# SSR_Switch.net
KiCad netlist of a schematic drawn in EasyEDA Pro
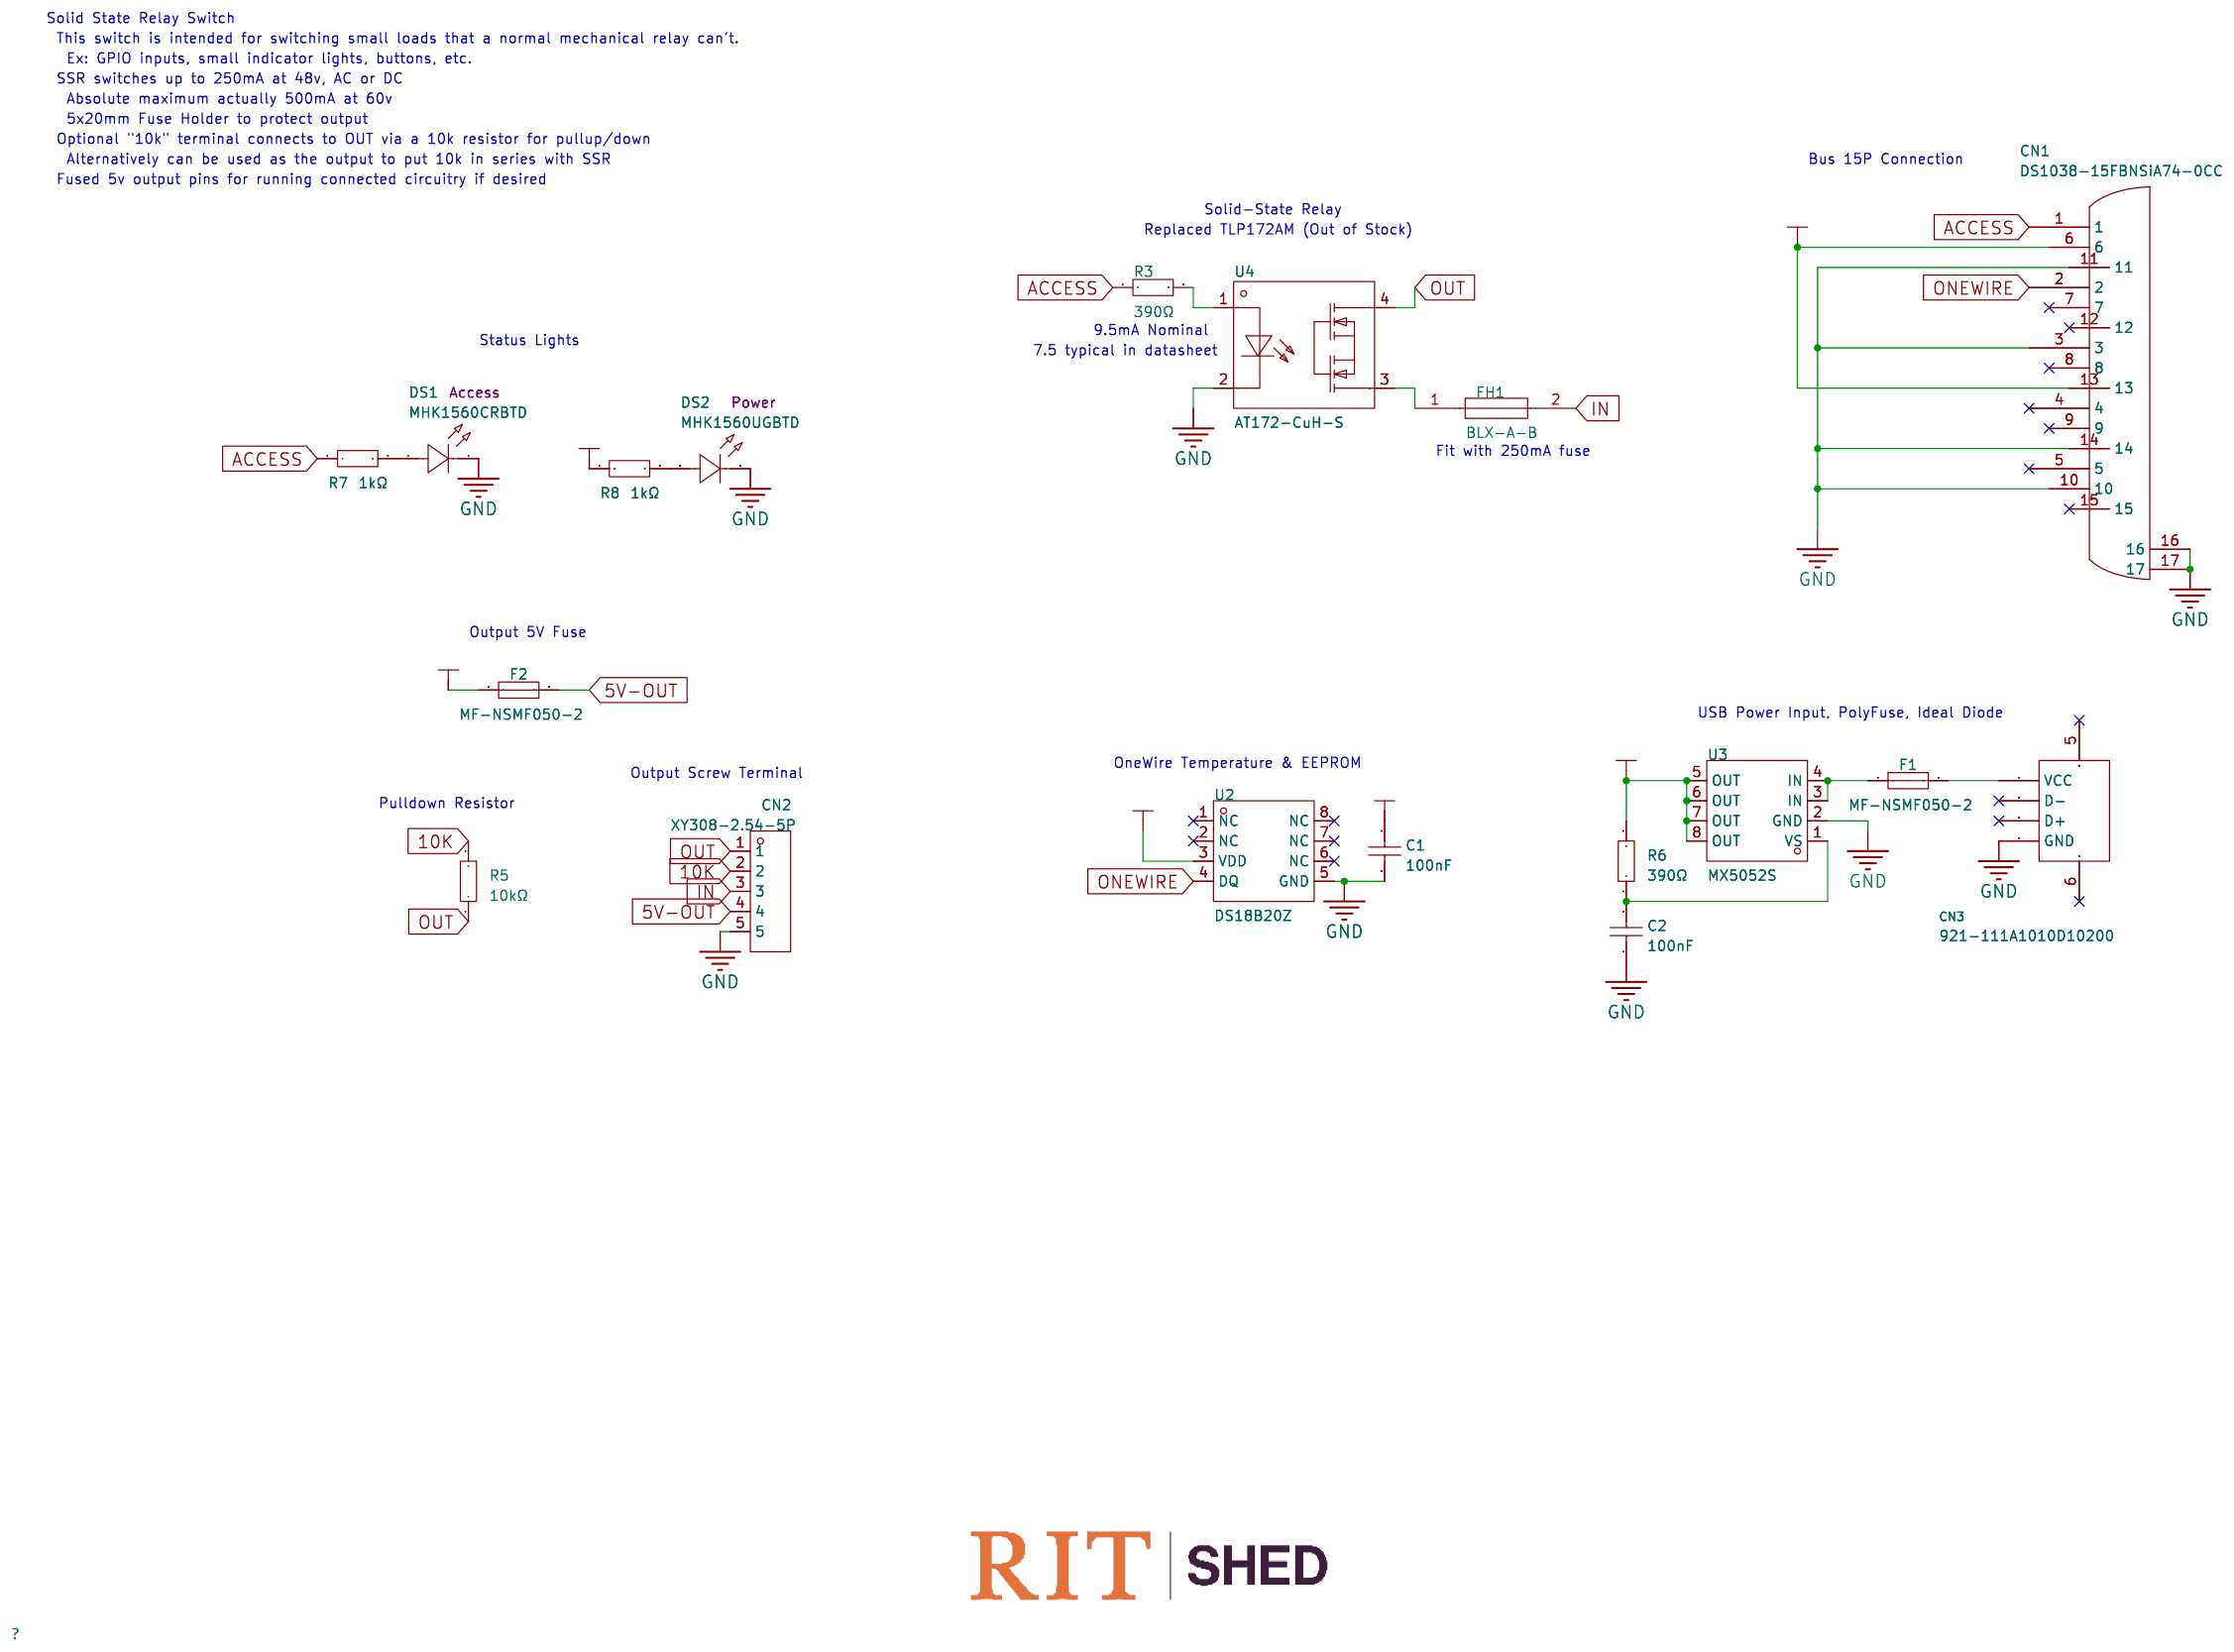
[diagram p0: schematic sheet]

(export (version "E")
  (design (tool "Eeschema 10.0.6"))
  (components
    (comp (ref "C1")
      (value "100nF")
      (footprint "easyedapro:C0805")
      (description "Capacitance:100nF Tolerance:±10% Tolerance:±10% Voltage Rating:100V Temperature Coefficient:X7R")
      (fields
        (field (name "Manufacturer Part") "CL21B104KCFNNNE")
        (field (name "Manufacturer") "SAMSUNG(三星)")
      )
      (libsource (lib "easyedapro") (part "CL21B104KCFNNNE"))
    )
    (comp (ref "C2")
      (value "100nF")
      (footprint "easyedapro:C0805")
      (description "Capacitance:100nF Tolerance:±10% Tolerance:±10% Voltage Rating:100V Temperature Coefficient:X7R")
      (fields
        (field (name "Manufacturer Part") "CL21B104KCFNNNE")
        (field (name "Manufacturer") "SAMSUNG(三星)")
      )
      (libsource (lib "easyedapro") (part "CL21B104KCFNNNE"))
    )
    (comp (ref "CN1")
      (value "DS1038-15FBNSiA74-0CC")
      (footprint "easyedapro:DSUB-TH_DS1038-15FBNSIA74-0CC")
      (fields (field (name "Manufacturer") "CONNFLY"))
      (libsource (lib "easyedapro") (part "DS1038-15FBNSIA74-0CC"))
    )
    (comp (ref "CN2")
      (value "XY308-2.54-5P")
      (footprint "easyedapro:CONN-TH_XY308-2.54-5P")
      (fields (field (name "Manufacturer") "XINLAIYA(新莱亚)"))
      (libsource (lib "easyedapro") (part "XY308-2.54-5P"))
    )
    (comp (ref "CN3")
      (value "921-111A1010D10200")
      (footprint "easyedapro:USB-B_TH_USB-B-FEMALE-90")
      (fields (field (name "Manufacturer") "精拓金"))
      (libsource (lib "easyedapro") (part "USB-B-Female-90"))
    )
    (comp (ref "DS1")
      (value "MHK1560CRBTD")
      (footprint "easyedapro:LED-TH_MHK1560UGBTD")
      (fields (field (name "Manufacturer") "MEIHUA(美华)") (field (name "Note") "Access"))
      (libsource (lib "easyedapro") (part "MHK1560CGBTD"))
    )
    (comp (ref "DS2")
      (value "MHK1560UGBTD")
      (footprint "easyedapro:LED-TH_MHK1560UGBTD")
      (fields (field (name "Manufacturer") "MEIHUA(美华)") (field (name "Note") "Power"))
      (libsource (lib "easyedapro") (part "MHK1560UGBTD"))
    )
    (comp (ref "F1")
      (value "MF-NSMF050-2")
      (footprint "easyedapro:F1206")
      (fields (field (name "Manufacturer") "BOURNS"))
      (libsource (lib "easyedapro") (part "MF-NSMF050-2"))
    )
    (comp (ref "F2")
      (value "MF-NSMF050-2")
      (footprint "easyedapro:F1206")
      (fields (field (name "Manufacturer") "BOURNS"))
      (libsource (lib "easyedapro") (part "MF-NSMF050-2"))
    )
    (comp (ref "FH1")
      (value "BLX-A-B")
      (footprint "easyedapro:FUSE-TH_BLX-A-B")
      (fields (field (name "Manufacturer") "XFCN(兴飞)"))
      (libsource (lib "easyedapro") (part "BLX-A-B"))
    )
    (comp (ref "R3")
      (value "390Ω")
      (footprint "easyedapro:R0805")
      (fields
        (field (name "Manufacturer Part") "0805W8F3900T5E")
        (field (name "Manufacturer") "UNI-ROYAL(厚声)")
      )
      (libsource (lib "easyedapro") (part "0805W8F3900T5E"))
    )
    (comp (ref "R5")
      (value "10kΩ")
      (footprint "easyedapro:R0805")
      (fields
        (field (name "Manufacturer Part") "0805W8F1002T5E")
        (field (name "Manufacturer") "UNI-ROYAL(厚声)")
      )
      (libsource (lib "easyedapro") (part "0805W8F1002T5E"))
    )
    (comp (ref "R6")
      (value "390Ω")
      (footprint "easyedapro:R0805")
      (fields
        (field (name "Manufacturer Part") "0805W8F3900T5E")
        (field (name "Manufacturer") "UNI-ROYAL(厚声)")
      )
      (libsource (lib "easyedapro") (part "0805W8F3900T5E"))
    )
    (comp (ref "R7")
      (value "1kΩ")
      (footprint "easyedapro:R0805")
      (fields
        (field (name "Manufacturer Part") "0805W8F1001T5E")
        (field (name "Manufacturer") "UNI-ROYAL(厚声)")
      )
      (libsource (lib "easyedapro") (part "0805W8F1001T5E"))
    )
    (comp (ref "R8")
      (value "1kΩ")
      (footprint "easyedapro:R0805")
      (fields
        (field (name "Manufacturer Part") "0805W8F1001T5E")
        (field (name "Manufacturer") "UNI-ROYAL(厚声)")
      )
      (libsource (lib "easyedapro") (part "0805W8F1001T5E"))
    )
    (comp (ref "U2")
      (value "DS18B20Z")
      (footprint "easyedapro:SOP-8_L4.9-W3.9-P1.27-LS6.0-BL")
      (description "Resolution:±0.4°C Resolution:±0.4°C Supply Voltage:2.5V~5.5V Supply Voltage:2.5V~5.5V")
      (fields (field (name "Manufacturer") "UMW(友台半导体)"))
      (libsource (lib "easyedapro") (part "DS18B20Z"))
    )
    (comp (ref "U3")
      (value "MX5052S")
      (footprint "easyedapro:SOP-8_L4.9-W3.9-P1.27-LS6.0-BL")
      (fields (field (name "Manufacturer") "Wuxi Maxinmicro(无锡明芯微)"))
      (libsource (lib "easyedapro") (part "MX5052S"))
    )
    (comp (ref "U4")
      (value "AT172-CuH-S")
      (footprint "easyedapro:SOP-4_L4.6-W4.2-P2.54-LS7.1-BL")
      (fields (field (name "Manufacturer") "AOTE(奥特)"))
      (libsource (lib "easyedapro") (part "AT172-CUH-S"))
    )
  )
  (nets
    (net (code "1") (name "+5V-BUS") (class "Default")
      (node (ref "C1") (pin "2") (pinfunction "2_2") (pintype "input"))
      (node (ref "CN1") (pin "13") (pinfunction "13_13") (pintype "unspecified"))
      (node (ref "CN1") (pin "6") (pinfunction "6_6") (pintype "unspecified"))
      (node (ref "F2") (pin "1") (pinfunction "1_1") (pintype "unspecified"))
      (node (ref "R6") (pin "2") (pinfunction "2_2") (pintype "input"))
      (node (ref "R8") (pin "1") (pinfunction "1_1") (pintype "input"))
      (node (ref "U2") (pin "3") (pinfunction "VDD_3") (pintype "unspecified"))
      (node (ref "U3") (pin "5") (pinfunction "OUT_5") (pintype "unspecified"))
      (node (ref "U3") (pin "6") (pinfunction "OUT_6") (pintype "unspecified"))
      (node (ref "U3") (pin "7") (pinfunction "OUT_7") (pintype "unspecified"))
      (node (ref "U3") (pin "8") (pinfunction "OUT_8") (pintype "unspecified"))
    )
    (net (code "2") (name "5V-OUT") (class "Default")
      (node (ref "CN2") (pin "4") (pinfunction "4_4") (pintype "unspecified"))
      (node (ref "F2") (pin "2") (pinfunction "2_2") (pintype "unspecified"))
    )
    (net (code "3") (name "10K") (class "Default")
      (node (ref "CN2") (pin "2") (pinfunction "2_2") (pintype "unspecified"))
      (node (ref "R5") (pin "2") (pinfunction "2_2") (pintype "input"))
    )
    (net (code "4") (name "ACCESS") (class "Default")
      (node (ref "CN1") (pin "1") (pinfunction "1_1") (pintype "unspecified"))
      (node (ref "R3") (pin "1") (pinfunction "1_1") (pintype "input"))
      (node (ref "R7") (pin "1") (pinfunction "1_1") (pintype "input"))
    )
    (net (code "5") (name "GND") (class "Default")
      (node (ref "C1") (pin "1") (pinfunction "1_1") (pintype "input"))
      (node (ref "C2") (pin "1") (pinfunction "1_1") (pintype "input"))
      (node (ref "CN1") (pin "10") (pinfunction "10_10") (pintype "unspecified"))
      (node (ref "CN1") (pin "11") (pinfunction "11_11") (pintype "unspecified"))
      (node (ref "CN1") (pin "14") (pinfunction "14_14") (pintype "unspecified"))
      (node (ref "CN1") (pin "16") (pinfunction "16_16") (pintype "unspecified"))
      (node (ref "CN1") (pin "17") (pinfunction "17_17") (pintype "unspecified"))
      (node (ref "CN1") (pin "3") (pinfunction "3_3") (pintype "unspecified"))
      (node (ref "CN2") (pin "5") (pinfunction "5_5") (pintype "unspecified"))
      (node (ref "CN3") (pin "4") (pinfunction "GND_4") (pintype "input"))
      (node (ref "DS1") (pin "1") (pinfunction "K_1") (pintype "unspecified"))
      (node (ref "DS2") (pin "1") (pinfunction "K_1") (pintype "unspecified"))
      (node (ref "U2") (pin "5") (pinfunction "GND_5") (pintype "unspecified"))
      (node (ref "U3") (pin "2") (pinfunction "GND_2") (pintype "unspecified"))
      (node (ref "U4") (pin "2") (pinfunction "K_2") (pintype "unspecified"))
    )
    (net (code "6") (name "IN") (class "Default")
      (node (ref "CN2") (pin "3") (pinfunction "3_3") (pintype "unspecified"))
      (node (ref "FH1") (pin "2") (pinfunction "2_2") (pintype "unspecified"))
    )
    (net (code "7") (name "Net-(CN3-VCC)") (class "Default")
      (node (ref "CN3") (pin "1") (pinfunction "VCC_1") (pintype "input"))
      (node (ref "F1") (pin "2") (pinfunction "2_2") (pintype "unspecified"))
    )
    (net (code "8") (name "Net-(DS1-A)") (class "Default")
      (node (ref "DS1") (pin "2") (pinfunction "A_2") (pintype "unspecified"))
      (node (ref "R7") (pin "2") (pinfunction "2_2") (pintype "input"))
    )
    (net (code "9") (name "Net-(DS2-A)") (class "Default")
      (node (ref "DS2") (pin "2") (pinfunction "A_2") (pintype "unspecified"))
      (node (ref "R8") (pin "2") (pinfunction "2_2") (pintype "input"))
    )
    (net (code "10") (name "Net-(F1-Pad1)") (class "Default")
      (node (ref "F1") (pin "1") (pinfunction "1_1") (pintype "unspecified"))
      (node (ref "U3") (pin "3") (pinfunction "IN_3") (pintype "unspecified"))
      (node (ref "U3") (pin "4") (pinfunction "IN_4") (pintype "unspecified"))
    )
    (net (code "11") (name "Net-(FH1-Pad1)") (class "Default")
      (node (ref "FH1") (pin "1") (pinfunction "1_1") (pintype "unspecified"))
      (node (ref "U4") (pin "3") (pinfunction "3_3") (pintype "unspecified"))
    )
    (net (code "12") (name "Net-(R3-Pad2)") (class "Default")
      (node (ref "R3") (pin "2") (pinfunction "2_2") (pintype "input"))
      (node (ref "U4") (pin "1") (pinfunction "1_1") (pintype "unspecified"))
    )
    (net (code "13") (name "Net-(U3-VS)") (class "Default")
      (node (ref "C2") (pin "2") (pinfunction "2_2") (pintype "input"))
      (node (ref "R6") (pin "1") (pinfunction "1_1") (pintype "input"))
      (node (ref "U3") (pin "1") (pinfunction "VS_1") (pintype "unspecified"))
    )
    (net (code "14") (name "ONEWIRE") (class "Default")
      (node (ref "CN1") (pin "2") (pinfunction "2_2") (pintype "unspecified"))
      (node (ref "U2") (pin "4") (pinfunction "DQ_4") (pintype "unspecified"))
    )
    (net (code "15") (name "OUT") (class "Default")
      (node (ref "CN2") (pin "1") (pinfunction "1_1") (pintype "unspecified"))
      (node (ref "R5") (pin "1") (pinfunction "1_1") (pintype "input"))
      (node (ref "U4") (pin "4") (pinfunction "4_4") (pintype "unspecified"))
    )
    (net (code "16") (name "unconnected-(CN1-Pad4)") (class "Default")
      (node (ref "CN1") (pin "4") (pinfunction "4_4") (pintype "unspecified+no_connect"))
    )
    (net (code "17") (name "unconnected-(CN1-Pad5)") (class "Default")
      (node (ref "CN1") (pin "5") (pinfunction "5_5") (pintype "unspecified+no_connect"))
    )
    (net (code "18") (name "unconnected-(CN1-Pad7)") (class "Default")
      (node (ref "CN1") (pin "7") (pinfunction "7_7") (pintype "unspecified+no_connect"))
    )
    (net (code "19") (name "unconnected-(CN1-Pad8)") (class "Default")
      (node (ref "CN1") (pin "8") (pinfunction "8_8") (pintype "unspecified+no_connect"))
    )
    (net (code "20") (name "unconnected-(CN1-Pad9)") (class "Default")
      (node (ref "CN1") (pin "9") (pinfunction "9_9") (pintype "unspecified+no_connect"))
    )
    (net (code "21") (name "unconnected-(CN1-Pad12)") (class "Default")
      (node (ref "CN1") (pin "12") (pinfunction "12_12") (pintype "unspecified+no_connect"))
    )
    (net (code "22") (name "unconnected-(CN1-Pad15)") (class "Default")
      (node (ref "CN1") (pin "15") (pinfunction "15_15") (pintype "unspecified+no_connect"))
    )
    (net (code "23") (name "unconnected-(CN3-D+-Pad3)") (class "Default")
      (node (ref "CN3") (pin "3") (pinfunction "D+_3") (pintype "input+no_connect"))
    )
    (net (code "24") (name "unconnected-(CN3-D--Pad2)") (class "Default")
      (node (ref "CN3") (pin "2") (pinfunction "D-_2") (pintype "input+no_connect"))
    )
    (net (code "25") (name "unconnected-(CN3-SH1-Pad5)") (class "Default")
      (node (ref "CN3") (pin "5") (pinfunction "SH1_5") (pintype "input+no_connect"))
    )
    (net (code "26") (name "unconnected-(CN3-SH2-Pad6)") (class "Default")
      (node (ref "CN3") (pin "6") (pinfunction "SH2_6") (pintype "input+no_connect"))
    )
    (net (code "27") (name "unconnected-(U2-NC-Pad1)") (class "Default")
      (node (ref "U2") (pin "1") (pinfunction "NC_1") (pintype "unspecified+no_connect"))
    )
    (net (code "28") (name "unconnected-(U2-NC-Pad2)") (class "Default")
      (node (ref "U2") (pin "2") (pinfunction "NC_2") (pintype "unspecified+no_connect"))
    )
    (net (code "29") (name "unconnected-(U2-NC-Pad6)") (class "Default")
      (node (ref "U2") (pin "6") (pinfunction "NC_6") (pintype "unspecified+no_connect"))
    )
    (net (code "30") (name "unconnected-(U2-NC-Pad7)") (class "Default")
      (node (ref "U2") (pin "7") (pinfunction "NC_7") (pintype "unspecified+no_connect"))
    )
    (net (code "31") (name "unconnected-(U2-NC-Pad8)") (class "Default")
      (node (ref "U2") (pin "8") (pinfunction "NC_8") (pintype "unspecified+no_connect"))
    )
  )
)
